# controller_board.net
KiCad netlist of a schematic drawn in EAGLE
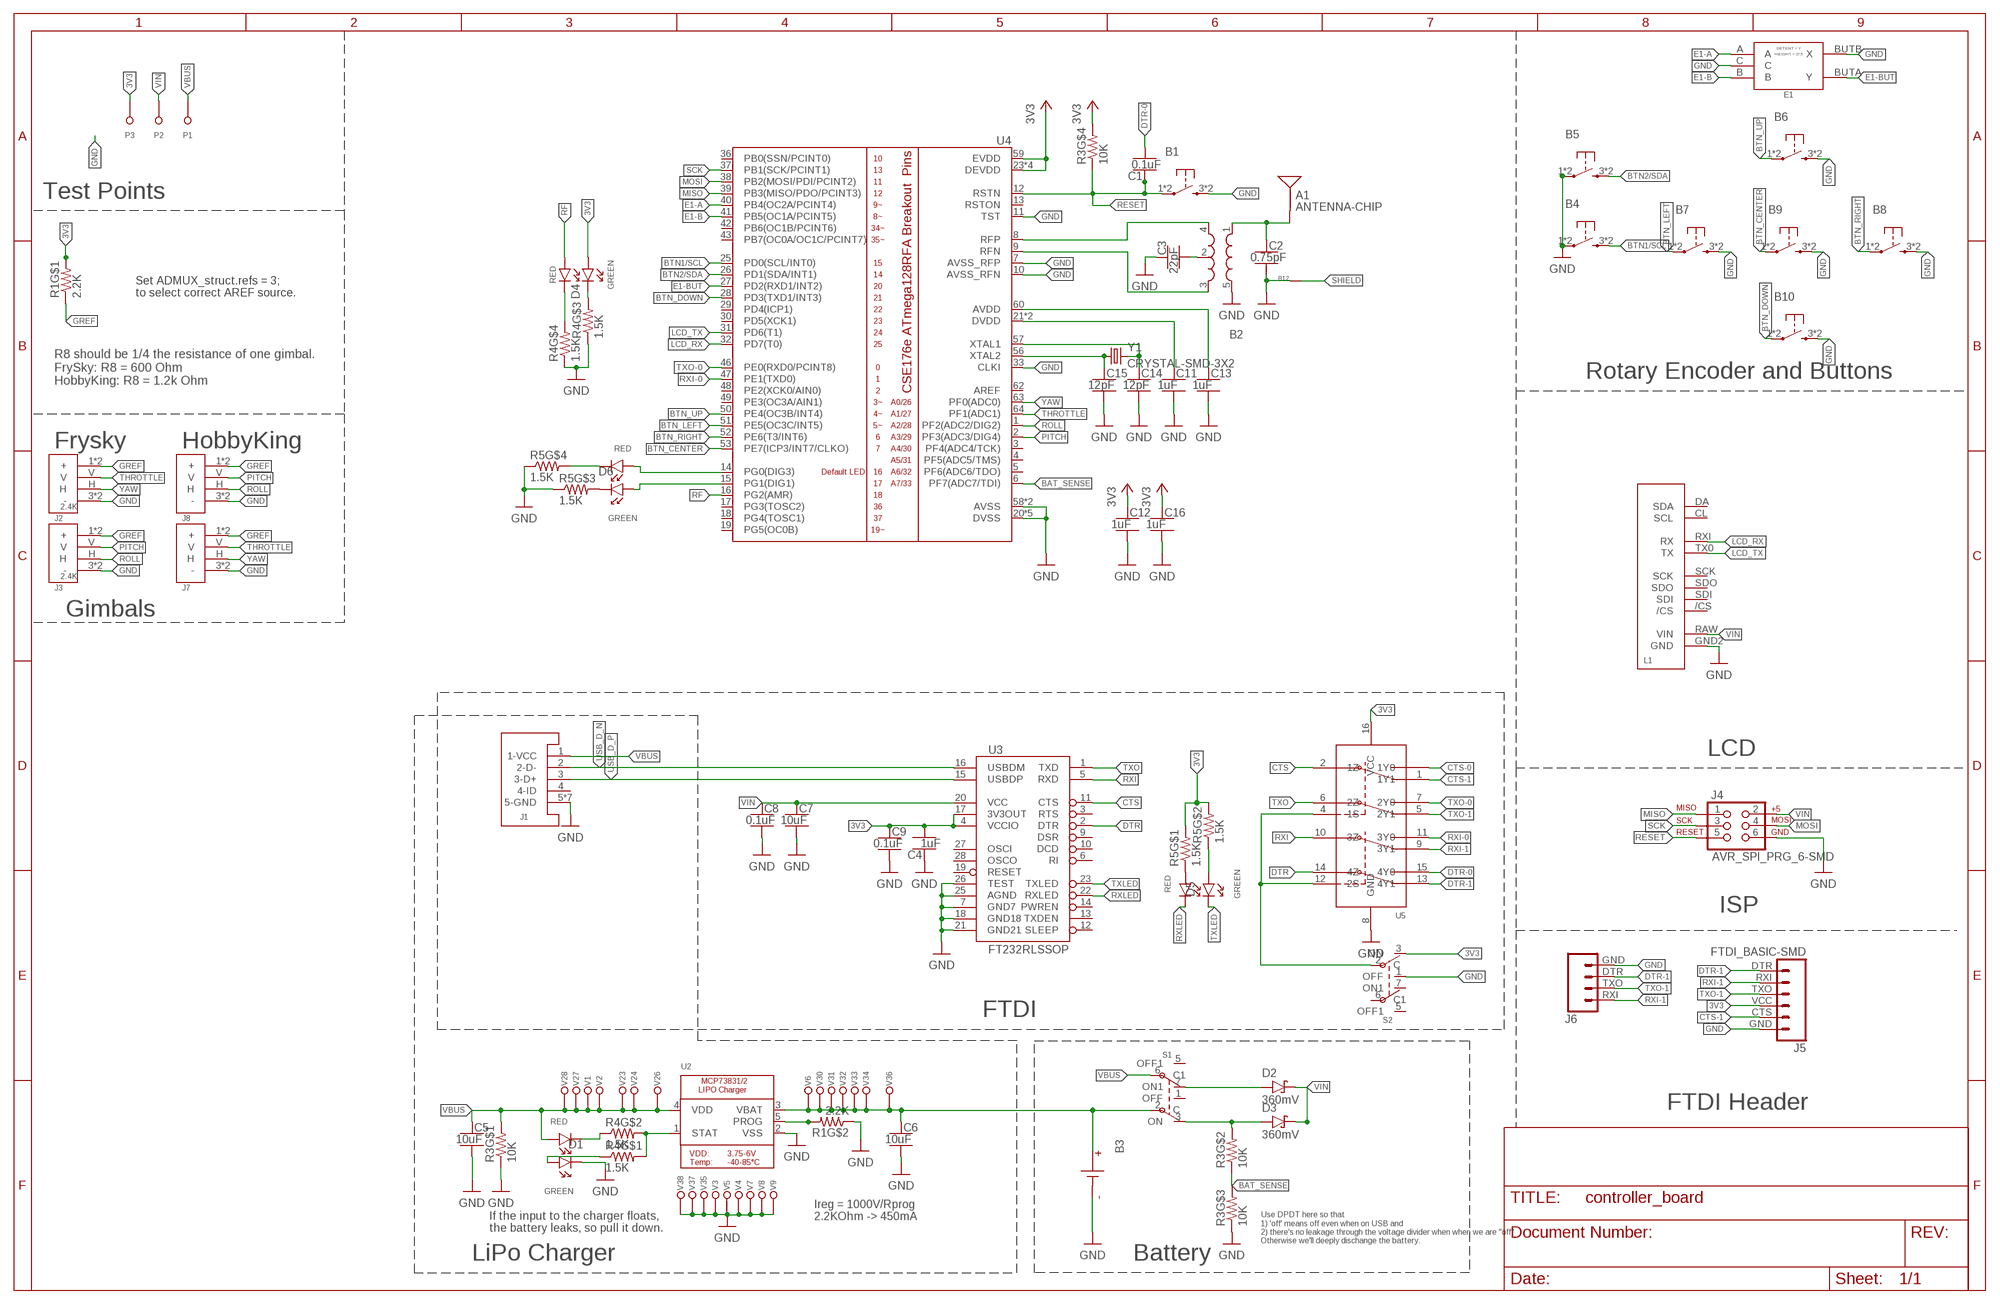
[diagram p0: schematic, sheet 1]

(export (version "E")
  (design (tool "Eeschema 10.0.6"))
  (components
    (comp (ref "A1")
      (value "ANTENNA-CHIP")
      (footprint "eagle-import:ANTENNA-CHIP")
      (fields (field (name "MFR") "Linx Technologies Inc.") (field (name "MPN") "ANT-2.45-CHP-T"))
      (libsource (lib "eagle-import") (part "ANTENNA-CHIP"))
    )
    (comp (ref "B1")
      (value "PUSHBUTTON_-4.5X4.5")
      (footprint "eagle-import:4.5MM_TACTILE_SWITCH_TL3305AF160QG")
      (fields (field (name "MFR") "E-Switch") (field (name "MPN") "TL3305AF160QG"))
      (libsource (lib "eagle-import") (part "PUSHBUTTON_-4.5X4.5"))
    )
    (comp (ref "B2")
      (value "BALUN0805")
      (footprint "eagle-import:BALUN")
      (fields (field (name "MFR") "Wurth Electronics Inc.") (field (name "MPN") "748421245"))
      (libsource (lib "eagle-import") (part "BALUN0805"))
    )
    (comp (ref "B3")
      (value "BATTERY-SMD")
      (footprint "eagle-import:MOLEX-BATTERY-CONNECTOR-SMD-51005-2P")
      (fields (field (name "MFR") "UNKNOWN"))
      (libsource (lib "eagle-import") (part "BATTERY-SMD"))
    )
    (comp (ref "B4")
      (value "PUSHBUTTON_-4.5X4.5")
      (footprint "eagle-import:4.5MM_TACTILE_SWITCH_TL3305AF160QG")
      (fields (field (name "MFR") "E-Switch") (field (name "MPN") "TL3305AF160QG"))
      (libsource (lib "eagle-import") (part "PUSHBUTTON_-4.5X4.5"))
    )
    (comp (ref "B5")
      (value "PUSHBUTTON_-4.5X4.5")
      (footprint "eagle-import:4.5MM_TACTILE_SWITCH_TL3305AF160QG")
      (fields (field (name "MFR") "E-Switch") (field (name "MPN") "TL3305AF160QG"))
      (libsource (lib "eagle-import") (part "PUSHBUTTON_-4.5X4.5"))
    )
    (comp (ref "B6")
      (value "PUSHBUTTON_-4.5X4.5")
      (footprint "eagle-import:4.5MM_TACTILE_SWITCH_TL3305AF160QG")
      (fields (field (name "MFR") "E-Switch") (field (name "MPN") "TL3305AF160QG"))
      (libsource (lib "eagle-import") (part "PUSHBUTTON_-4.5X4.5"))
    )
    (comp (ref "B7")
      (value "PUSHBUTTON_-4.5X4.5")
      (footprint "eagle-import:4.5MM_TACTILE_SWITCH_TL3305AF160QG")
      (fields (field (name "MFR") "E-Switch") (field (name "MPN") "TL3305AF160QG"))
      (libsource (lib "eagle-import") (part "PUSHBUTTON_-4.5X4.5"))
    )
    (comp (ref "B8")
      (value "PUSHBUTTON_-4.5X4.5")
      (footprint "eagle-import:4.5MM_TACTILE_SWITCH_TL3305AF160QG")
      (fields (field (name "MFR") "E-Switch") (field (name "MPN") "TL3305AF160QG"))
      (libsource (lib "eagle-import") (part "PUSHBUTTON_-4.5X4.5"))
    )
    (comp (ref "B9")
      (value "PUSHBUTTON_-4.5X4.5")
      (footprint "eagle-import:4.5MM_TACTILE_SWITCH_TL3305AF160QG")
      (fields (field (name "MFR") "E-Switch") (field (name "MPN") "TL3305AF160QG"))
      (libsource (lib "eagle-import") (part "PUSHBUTTON_-4.5X4.5"))
    )
    (comp (ref "B10")
      (value "PUSHBUTTON_-4.5X4.5")
      (footprint "eagle-import:4.5MM_TACTILE_SWITCH_TL3305AF160QG")
      (fields (field (name "MFR") "E-Switch") (field (name "MPN") "TL3305AF160QG"))
      (libsource (lib "eagle-import") (part "PUSHBUTTON_-4.5X4.5"))
    )
    (comp (ref "B12")
      (value "NET_BRIDGE")
      (footprint "eagle-import:NET_BRIDGE")
      (libsource (lib "eagle-import") (part "NET_BRIDGE"))
    )
    (comp (ref "C1")
      (value "0.1uF")
      (footprint "eagle-import:CAPC1608X100")
      (fields (field (name "MFR") "KEMET") (field (name "MPN") "C0603C104K8RACTU"))
      (libsource (lib "eagle-import") (part "CAPACITOR-NP_SMD-0603_CERAMIC-0.1UF"))
    )
    (comp (ref "C2")
      (value "0.75pF")
      (footprint "eagle-import:CAPC1608X100")
      (fields (field (name "MFR") "Yageo") (field (name "MPN") "CC0603BRNPO9BNR75"))
      (libsource (lib "eagle-import") (part "CAPACITOR-NP_SMD-0603_CERAMIC-0.75PF"))
    )
    (comp (ref "C3")
      (value "22pF")
      (footprint "eagle-import:CAPC1608X100")
      (fields (field (name "MFR") "AVX Corporation") (field (name "MPN") "06036A220KAT2A"))
      (libsource (lib "eagle-import") (part "CAPACITOR-NP_SMD-0603_CERAMIC-22PF"))
    )
    (comp (ref "C4")
      (value "1uF")
      (footprint "eagle-import:CAPC1608X100")
      (fields (field (name "MFR") "Samsung Electro-Mechanics") (field (name "MPN") "CL10A105KP8NNNC"))
      (libsource (lib "eagle-import") (part "CAPACITOR-NP_SMD-0603_CERAMIC-1UF"))
    )
    (comp (ref "C5")
      (value "10uF")
      (footprint "eagle-import:CAPC1608X100")
      (fields (field (name "MFR") "Samsung Electro-Mechanics") (field (name "MPN") "CL10A106MQ8NNNC"))
      (libsource (lib "eagle-import") (part "CAPACITOR-NP_SMD-0603_CERAMIC-10UF"))
    )
    (comp (ref "C6")
      (value "10uF")
      (footprint "eagle-import:CAPC1608X100")
      (fields (field (name "MFR") "Samsung Electro-Mechanics") (field (name "MPN") "CL10A106MQ8NNNC"))
      (libsource (lib "eagle-import") (part "CAPACITOR-NP_SMD-0603_CERAMIC-10UF"))
    )
    (comp (ref "C7")
      (value "10uF")
      (footprint "eagle-import:CAPC1608X100")
      (fields (field (name "MFR") "Samsung Electro-Mechanics") (field (name "MPN") "CL10A106MQ8NNNC"))
      (libsource (lib "eagle-import") (part "CAPACITOR-NP_SMD-0603_CERAMIC-10UF"))
    )
    (comp (ref "C8")
      (value "0.1uF")
      (footprint "eagle-import:CAPC1608X100")
      (fields (field (name "MFR") "KEMET") (field (name "MPN") "C0603C104K8RACTU"))
      (libsource (lib "eagle-import") (part "CAPACITOR-NP_SMD-0603_CERAMIC-0.1UF"))
    )
    (comp (ref "C9")
      (value "0.1uF")
      (footprint "eagle-import:CAPC1608X100")
      (fields (field (name "MFR") "KEMET") (field (name "MPN") "C0603C104K8RACTU"))
      (libsource (lib "eagle-import") (part "CAPACITOR-NP_SMD-0603_CERAMIC-0.1UF"))
    )
    (comp (ref "C11")
      (value "1uF")
      (footprint "eagle-import:CAPC1608X100")
      (fields (field (name "MFR") "Samsung Electro-Mechanics") (field (name "MPN") "CL10A105KP8NNNC"))
      (libsource (lib "eagle-import") (part "CAPACITOR-NP_SMD-0603_CERAMIC-1UF"))
    )
    (comp (ref "C12")
      (value "1uF")
      (footprint "eagle-import:CAPC1608X100")
      (fields (field (name "MFR") "Samsung Electro-Mechanics") (field (name "MPN") "CL10A105KP8NNNC"))
      (libsource (lib "eagle-import") (part "CAPACITOR-NP_SMD-0603_CERAMIC-1UF"))
    )
    (comp (ref "C13")
      (value "1uF")
      (footprint "eagle-import:CAPC1608X100")
      (fields (field (name "MFR") "Samsung Electro-Mechanics") (field (name "MPN") "CL10A105KP8NNNC"))
      (libsource (lib "eagle-import") (part "CAPACITOR-NP_SMD-0603_CERAMIC-1UF"))
    )
    (comp (ref "C14")
      (value "12pF")
      (footprint "eagle-import:CAPC1608X100")
      (fields (field (name "MFR") "Vishay Vitramon") (field (name "MPN") "VJ0603A120FXQCW1BC"))
      (libsource (lib "eagle-import") (part "CAPACITOR-NP_SMD-0603_CERAMIC-12PF"))
    )
    (comp (ref "C15")
      (value "12pF")
      (footprint "eagle-import:CAPC1608X100")
      (fields (field (name "MFR") "Vishay Vitramon") (field (name "MPN") "VJ0603A120FXQCW1BC"))
      (libsource (lib "eagle-import") (part "CAPACITOR-NP_SMD-0603_CERAMIC-12PF"))
    )
    (comp (ref "C16")
      (value "1uF")
      (footprint "eagle-import:CAPC1608X100")
      (fields (field (name "MFR") "Samsung Electro-Mechanics") (field (name "MPN") "CL10A105KP8NNNC"))
      (libsource (lib "eagle-import") (part "CAPACITOR-NP_SMD-0603_CERAMIC-1UF"))
    )
    (comp (ref "D1")
      (value "LED-2X-GREEN/RED-1.6X1.5MM")
      (footprint "eagle-import:LED-2X-LITE-ON-1.6MMX1.5MM")
      (fields
        (field (name "COLOR2") "GREEN")
        (field (name "COLOR1") "RED")
        (field (name "MFR") "Lite-On Inc.")
        (field (name "MPN") "LTST-C195TGKRKT")
      )
      (libsource (lib "eagle-import") (part "LED-2X-GREEN/RED-1.6X1.5MM"))
    )
    (comp (ref "D2")
      (value "360mV")
      (footprint "eagle-import:SODFL3516X96")
      (fields
        (field (name "MFR") "Toshiba Semiconductor and Storage")
        (field (name "MPN") "CRS08(TE85L,Q,M)")
      )
      (libsource (lib "eagle-import") (part "DIODE-SCHOTTKY_-SMD-SOD123"))
    )
    (comp (ref "D3")
      (value "360mV")
      (footprint "eagle-import:SODFL3516X96")
      (fields
        (field (name "MFR") "Toshiba Semiconductor and Storage")
        (field (name "MPN") "CRS08(TE85L,Q,M)")
      )
      (libsource (lib "eagle-import") (part "DIODE-SCHOTTKY_-SMD-SOD123"))
    )
    (comp (ref "D4")
      (value "LED-2X-GREEN/RED-1.6X1.5MM")
      (footprint "eagle-import:LED-2X-LITE-ON-1.6MMX1.5MM")
      (fields
        (field (name "COLOR2") "GREEN")
        (field (name "COLOR1") "RED")
        (field (name "MFR") "Lite-On Inc.")
        (field (name "MPN") "LTST-C195TGKRKT")
      )
      (libsource (lib "eagle-import") (part "LED-2X-GREEN/RED-1.6X1.5MM"))
    )
    (comp (ref "D5")
      (value "LED-2X-GREEN/RED-1.6X1.5MM")
      (footprint "eagle-import:LED-2X-LITE-ON-1.6MMX1.5MM")
      (fields
        (field (name "COLOR2") "GREEN")
        (field (name "COLOR1") "RED")
        (field (name "MFR") "Lite-On Inc.")
        (field (name "MPN") "LTST-C195TGKRKT")
      )
      (libsource (lib "eagle-import") (part "LED-2X-GREEN/RED-1.6X1.5MM"))
    )
    (comp (ref "D6")
      (value "LED-2X-GREEN/RED-1.6X1.5MM")
      (footprint "eagle-import:LED-2X-LITE-ON-1.6MMX1.5MM")
      (fields
        (field (name "COLOR2") "GREEN")
        (field (name "COLOR1") "RED")
        (field (name "MFR") "Lite-On Inc.")
        (field (name "MPN") "LTST-C195TGKRKT")
      )
      (libsource (lib "eagle-import") (part "LED-2X-GREEN/RED-1.6X1.5MM"))
    )
    (comp (ref "E1")
      (value "ROTARY-ENCODER-W/BUTTON-BOURNS-PEC12R-4217F")
      (footprint "eagle-import:BOURNS-PEC12R")
      (fields (field (name "DETENT") "Y") (field (name "HEIGHT") "17.5"))
      (libsource (lib "eagle-import") (part "ROTARY-ENCODER-W/BUTTON-BOURNS-PEC12R-4217F"))
    )
    (comp (ref "J1")
      (value "USB-MICROA-AMPHENOL-10118192-0001LF")
      (footprint "eagle-import:USB-MICROA-10118192-0001LF")
      (fields (field (name "MFR") "Amphenol ICC (FCI)") (field (name "MPN") "10118192-0001LF"))
      (libsource (lib "eagle-import") (part "USB-MICROA-AMPHENOL-10118192-0001LF"))
    )
    (comp (ref "J2")
      (value "2.4K")
      (footprint "eagle-import:JST-13-PTH")
      (fields (field (name "MFR") "TE Connectivity AMP Connectors") (field (name "MPN") "1-1735446-2"))
      (libsource (lib "eagle-import") (part "FRSKY-GIMBAL-FRYSKY"))
    )
    (comp (ref "J3")
      (value "2.4K")
      (footprint "eagle-import:JST-13-PTH")
      (fields
        (field (name "MFR") "TE Connectivity AMP Connectors")
        (field (name "MPN") "1-1735446-2")
        (field (name "SPICEPREFIX") "E")
      )
      (libsource (lib "eagle-import") (part "FRSKY-GIMBAL-FRYSKY"))
    )
    (comp (ref "J4")
      (value "AVR_SPI_PRG_6-SMD")
      (footprint "eagle-import:2X3-SMD")
      (fields (field (name "MFR") "Amphenol ICC (FCI)") (field (name "MPN") "95278-101A06LF"))
      (libsource (lib "eagle-import") (part "AVR_SPI_PRG_6-SMD"))
    )
    (comp (ref "J5")
      (value "FTDI_BASIC-SMD")
      (footprint "eagle-import:FTDI-BASIC-SMD")
      (fields (field (name "MFR") "Harwin Inc.") (field (name "MPN") "M20-8890645"))
      (libsource (lib "eagle-import") (part "FTDI_BASIC-SMD"))
    )
    (comp (ref "J6")
      (value "FTDI-4PIN-RIGHT-ANGLE-SMD")
      (footprint "eagle-import:HEADER-2X2-0.1IN-MALE-RIGHT-ANGLE-SMD")
      (fields (field (name "MFR") "Samtec Inc.") (field (name "MPN") "TSM-102-01-L-DH"))
      (libsource (lib "eagle-import") (part "FTDI-4PIN-RIGHT-ANGLE-SMD"))
    )
    (comp (ref "J7")
      (value "FRSKY-GIMBAL-2X-SERVO-SMD")
      (footprint "eagle-import:2X-SERVO-SMD")
      (fields (field (name "MFR") "Harwin Inc.") (field (name "MPN") "M20-8890645"))
      (libsource (lib "eagle-import") (part "FRSKY-GIMBAL-2X-SERVO-SMD"))
    )
    (comp (ref "J8")
      (value "FRSKY-GIMBAL-2X-SERVO-SMD")
      (footprint "eagle-import:2X-SERVO-SMD")
      (fields (field (name "MFR") "Harwin Inc.") (field (name "MPN") "M20-8890645"))
      (libsource (lib "eagle-import") (part "FRSKY-GIMBAL-2X-SERVO-SMD"))
    )
    (comp (ref "L1")
      (value "SPARKFUN_SERLCD_SERIAL_REDUCED-SMD")
      (footprint "eagle-import:SPARKFUN_SERLCD_16X2_REDUCED_SMD")
      (fields (field (name "MFR") "Harwin Inc.") (field (name "MPN") "M20-9991045"))
      (libsource (lib "eagle-import") (part "SPARKFUN_SERLCD_SERIAL_REDUCED-SMD"))
    )
    (comp (ref "P1")
      (value "TEST-POINT")
      (footprint "eagle-import:TEST-POINT-KEYSTONE-5000")
      (fields (field (name "MFR") "Keystone Electronics") (field (name "MPN") "5001"))
      (libsource (lib "eagle-import") (part "TEST-POINT"))
    )
    (comp (ref "P2")
      (value "TEST-POINT")
      (footprint "eagle-import:TEST-POINT-KEYSTONE-5000")
      (fields (field (name "MFR") "Keystone Electronics") (field (name "MPN") "5001"))
      (libsource (lib "eagle-import") (part "TEST-POINT"))
    )
    (comp (ref "P3")
      (value "TEST-POINT")
      (footprint "eagle-import:TEST-POINT-KEYSTONE-5000")
      (fields (field (name "MFR") "Keystone Electronics") (field (name "MPN") "5001"))
      (libsource (lib "eagle-import") (part "TEST-POINT"))
    )
    (comp (ref "R1")
      (value "2.2K")
      (footprint "eagle-import:RESCAXS50P200X100X45-8")
      (fields (field (name "MFR") "Panasonic Electronic Components") (field (name "MPN") "EXB-N8V221JX"))
      (libsource (lib "eagle-import") (part "RESISTOR-PACK-4X-2.2K"))
    )
    (comp (ref "R3")
      (value "10K")
      (footprint "eagle-import:RESCAXS50P200X100X45-8")
      (fields (field (name "MFR") "Panasonic Electronic Components") (field (name "MPN") "EXB-N8V103JX"))
      (libsource (lib "eagle-import") (part "RESISTOR-PACK-4X-10K"))
    )
    (comp (ref "R4")
      (value "1.5K")
      (footprint "eagle-import:RESCAXS50P200X100X45-8")
      (fields (field (name "MFR") "Panasonic Electronic Components") (field (name "MPN") "EXB-N8V152JX"))
      (libsource (lib "eagle-import") (part "RESISTOR-PACK-4X-1.5K"))
    )
    (comp (ref "R5")
      (value "1.5K")
      (footprint "eagle-import:RESCAXS50P200X100X45-8")
      (fields (field (name "MFR") "Panasonic Electronic Components") (field (name "MPN") "EXB-N8V152JX"))
      (libsource (lib "eagle-import") (part "RESISTOR-PACK-4X-1.5K"))
    )
    (comp (ref "S1")
      (value "SWITCH-DPDT-300MA-6V-SMD")
      (footprint "eagle-import:JS202011JCQN")
      (fields (field (name "MFR") "C&K") (field (name "MPN") "JS202011JCQN"))
      (libsource (lib "eagle-import") (part "SWITCH-DPDT-300MA-6V-SMD"))
    )
    (comp (ref "S2")
      (value "SWITCH-DPDT-300MA-6V-SMD")
      (footprint "eagle-import:JS202011JCQN")
      (fields (field (name "MFR") "C&K") (field (name "MPN") "JS202011JCQN"))
      (libsource (lib "eagle-import") (part "SWITCH-DPDT-300MA-6V-SMD"))
    )
    (comp (ref "U2")
      (value "MCP73831T-2ACI/OT")
      (footprint "eagle-import:SOT23-5")
      (fields (field (name "MFR") "Microchip Technology"))
      (libsource (lib "eagle-import") (part "MCP73831/2"))
    )
    (comp (ref "U3")
      (value "FT232RLSSOP")
      (footprint "eagle-import:SSOP28DB")
      (fields (field (name "MFR") "FTDI") (field (name "MPN") "FT232RL-REEL"))
      (libsource (lib "eagle-import") (part "FT232RLSSOP"))
    )
    (comp (ref "U4")
      (value "ATMEGA128RFA1")
      (footprint "eagle-import:QFN-64")
      (fields (field (name "MFR") "Microchip Technology") (field (name "MPN") "ATMEGA128RFA1-ZU"))
      (libsource (lib "eagle-import") (part "ATMEGA128RFA1"))
    )
    (comp (ref "U5")
      (value "DPDT-X2")
      (footprint "eagle-import:SOP65P640X110-16")
      (fields (field (name "MFR") "NXP USA Inc.") (field (name "MPN") "NX3L2467PW,118"))
      (libsource (lib "eagle-import") (part "DPDT-X2"))
    )
    (comp (ref "V1")
      (value "LOCKED-VIA-0.2")
      (footprint "eagle-import:VIA-0.2MM")
      (libsource (lib "eagle-import") (part "LOCKED-VIA-0.2"))
    )
    (comp (ref "V2")
      (value "LOCKED-VIA-0.2")
      (footprint "eagle-import:VIA-0.2MM")
      (libsource (lib "eagle-import") (part "LOCKED-VIA-0.2"))
    )
    (comp (ref "V3")
      (value "LOCKED-VIA-0.2")
      (footprint "eagle-import:VIA-0.2MM")
      (libsource (lib "eagle-import") (part "LOCKED-VIA-0.2"))
    )
    (comp (ref "V4")
      (value "LOCKED-VIA-0.2")
      (footprint "eagle-import:VIA-0.2MM")
      (libsource (lib "eagle-import") (part "LOCKED-VIA-0.2"))
    )
    (comp (ref "V5")
      (value "LOCKED-VIA-0.2")
      (footprint "eagle-import:VIA-0.2MM")
      (libsource (lib "eagle-import") (part "LOCKED-VIA-0.2"))
    )
    (comp (ref "V6")
      (value "LOCKED-VIA-0.2")
      (footprint "eagle-import:VIA-0.2MM")
      (libsource (lib "eagle-import") (part "LOCKED-VIA-0.2"))
    )
    (comp (ref "V7")
      (value "LOCKED-VIA-0.2")
      (footprint "eagle-import:VIA-0.2MM")
      (libsource (lib "eagle-import") (part "LOCKED-VIA-0.2"))
    )
    (comp (ref "V8")
      (value "LOCKED-VIA-0.2")
      (footprint "eagle-import:VIA-0.2MM")
      (libsource (lib "eagle-import") (part "LOCKED-VIA-0.2"))
    )
    (comp (ref "V9")
      (value "LOCKED-VIA-0.2")
      (footprint "eagle-import:VIA-0.2MM")
      (libsource (lib "eagle-import") (part "LOCKED-VIA-0.2"))
    )
    (comp (ref "V23")
      (value "LOCKED-VIA-0.2")
      (footprint "eagle-import:VIA-0.2MM")
      (libsource (lib "eagle-import") (part "LOCKED-VIA-0.2"))
    )
    (comp (ref "V24")
      (value "LOCKED-VIA-0.2")
      (footprint "eagle-import:VIA-0.2MM")
      (libsource (lib "eagle-import") (part "LOCKED-VIA-0.2"))
    )
    (comp (ref "V26")
      (value "LOCKED-VIA-0.2")
      (footprint "eagle-import:VIA-0.2MM")
      (libsource (lib "eagle-import") (part "LOCKED-VIA-0.2"))
    )
    (comp (ref "V27")
      (value "LOCKED-VIA-0.2")
      (footprint "eagle-import:VIA-0.2MM")
      (libsource (lib "eagle-import") (part "LOCKED-VIA-0.2"))
    )
    (comp (ref "V28")
      (value "LOCKED-VIA-0.2")
      (footprint "eagle-import:VIA-0.2MM")
      (libsource (lib "eagle-import") (part "LOCKED-VIA-0.2"))
    )
    (comp (ref "V30")
      (value "LOCKED-VIA-0.2")
      (footprint "eagle-import:VIA-0.2MM")
      (libsource (lib "eagle-import") (part "LOCKED-VIA-0.2"))
    )
    (comp (ref "V31")
      (value "LOCKED-VIA-0.2")
      (footprint "eagle-import:VIA-0.2MM")
      (libsource (lib "eagle-import") (part "LOCKED-VIA-0.2"))
    )
    (comp (ref "V32")
      (value "LOCKED-VIA-0.2")
      (footprint "eagle-import:VIA-0.2MM")
      (libsource (lib "eagle-import") (part "LOCKED-VIA-0.2"))
    )
    (comp (ref "V33")
      (value "LOCKED-VIA-0.2")
      (footprint "eagle-import:VIA-0.2MM")
      (libsource (lib "eagle-import") (part "LOCKED-VIA-0.2"))
    )
    (comp (ref "V34")
      (value "LOCKED-VIA-0.2")
      (footprint "eagle-import:VIA-0.2MM")
      (libsource (lib "eagle-import") (part "LOCKED-VIA-0.2"))
    )
    (comp (ref "V35")
      (value "LOCKED-VIA-0.2")
      (footprint "eagle-import:VIA-0.2MM")
      (libsource (lib "eagle-import") (part "LOCKED-VIA-0.2"))
    )
    (comp (ref "V36")
      (value "LOCKED-VIA-0.2")
      (footprint "eagle-import:VIA-0.2MM")
      (libsource (lib "eagle-import") (part "LOCKED-VIA-0.2"))
    )
    (comp (ref "V37")
      (value "LOCKED-VIA-0.2")
      (footprint "eagle-import:VIA-0.2MM")
      (libsource (lib "eagle-import") (part "LOCKED-VIA-0.2"))
    )
    (comp (ref "V38")
      (value "LOCKED-VIA-0.2")
      (footprint "eagle-import:VIA-0.2MM")
      (libsource (lib "eagle-import") (part "LOCKED-VIA-0.2"))
    )
    (comp (ref "Y1")
      (value "CRYSTAL-SMD-3X2")
      (footprint "eagle-import:OSCCC320X250X85")
      (fields (field (name "MFR") "Abracon LLC") (field (name "MPN") "ABM8-16.000MHZ-B2-T"))
      (libsource (lib "eagle-import") (part "CRYSTAL-SMD-3X2"))
    )
  )
  (nets
    (net (code "1") (name "3V3") (class "Default")
      (node (ref "C12") (pin "1") (pinfunction "1_1") (pintype "passive"))
      (node (ref "C16") (pin "1") (pinfunction "1_1") (pintype "passive"))
      (node (ref "C4") (pin "2") (pinfunction "2_2") (pintype "passive"))
      (node (ref "C9") (pin "1") (pinfunction "1_1") (pintype "passive"))
      (node (ref "D4") (pin "A1") (pinfunction "A1_A1") (pintype "passive"))
      (node (ref "J5") (pin "VCC") (pinfunction "4_VCC") (pintype "passive"))
      (node (ref "P3") (pin "T") (pinfunction "T_T") (pintype "bidirectional"))
      (node (ref "R1") (pin "5") (pinfunction "2_5") (pintype "passive"))
      (node (ref "R3") (pin "8") (pinfunction "2_8") (pintype "passive"))
      (node (ref "R5") (pin "5") (pinfunction "2_5") (pintype "passive"))
      (node (ref "R5") (pin "6") (pinfunction "2_6") (pintype "passive"))
      (node (ref "S2") (pin "3") (pinfunction "ON_3") (pintype "bidirectional"))
      (node (ref "U3") (pin "17") (pinfunction "3V3OUT_17") (pintype "output"))
      (node (ref "U3") (pin "4") (pinfunction "VCCIO_4") (pintype "power_in"))
      (node (ref "U4") (pin "23") (pinfunction "DEVDD_23") (pintype "bidirectional"))
      (node (ref "U4") (pin "34") (pinfunction "DEVDD_34") (pintype "bidirectional"))
      (node (ref "U4") (pin "44") (pinfunction "DEVDD_44") (pintype "bidirectional"))
      (node (ref "U4") (pin "54") (pinfunction "DEVDD_54") (pintype "bidirectional"))
      (node (ref "U4") (pin "59") (pinfunction "EVDD_59") (pintype "bidirectional"))
      (node (ref "U5") (pin "16") (pinfunction "VCC_16") (pintype "bidirectional"))
    )
    (net (code "2") (name "BAT_SENSE") (class "Default")
      (node (ref "R3") (pin "3") (pinfunction "1_3") (pintype "passive"))
      (node (ref "R3") (pin "7") (pinfunction "2_7") (pintype "passive"))
      (node (ref "U4") (pin "6") (pinfunction "PF7(ADC7/TDI)_6") (pintype "bidirectional"))
    )
    (net (code "3") (name "BTN1{slash}SCL") (class "Default")
      (node (ref "B4") (pin "3") (pinfunction "2_3") (pintype "passive"))
      (node (ref "B4") (pin "4") (pinfunction "2_4") (pintype "passive"))
      (node (ref "U4") (pin "25") (pinfunction "PD0(SCL/INT0)_25") (pintype "bidirectional"))
    )
    (net (code "4") (name "BTN2{slash}SDA") (class "Default")
      (node (ref "B5") (pin "3") (pinfunction "2_3") (pintype "passive"))
      (node (ref "B5") (pin "4") (pinfunction "2_4") (pintype "passive"))
      (node (ref "U4") (pin "26") (pinfunction "PD1(SDA/INT1)_26") (pintype "bidirectional"))
    )
    (net (code "5") (name "BTN_CENTER") (class "Default")
      (node (ref "B9") (pin "1") (pinfunction "1_1") (pintype "passive"))
      (node (ref "B9") (pin "2") (pinfunction "1_2") (pintype "passive"))
      (node (ref "U4") (pin "53") (pinfunction "PE7(ICP3/INT7/CLKO)_53") (pintype "bidirectional"))
    )
    (net (code "6") (name "BTN_DOWN") (class "Default")
      (node (ref "B10") (pin "1") (pinfunction "1_1") (pintype "passive"))
      (node (ref "B10") (pin "2") (pinfunction "1_2") (pintype "passive"))
      (node (ref "U4") (pin "28") (pinfunction "PD3(TXD1/INT3)_28") (pintype "bidirectional"))
    )
    (net (code "7") (name "BTN_LEFT") (class "Default")
      (node (ref "B7") (pin "1") (pinfunction "1_1") (pintype "passive"))
      (node (ref "B7") (pin "2") (pinfunction "1_2") (pintype "passive"))
      (node (ref "U4") (pin "51") (pinfunction "PE5(OC3C/INT5)_51") (pintype "bidirectional"))
    )
    (net (code "8") (name "BTN_RIGHT") (class "Default")
      (node (ref "B8") (pin "1") (pinfunction "1_1") (pintype "passive"))
      (node (ref "B8") (pin "2") (pinfunction "1_2") (pintype "passive"))
      (node (ref "U4") (pin "52") (pinfunction "PE6(T3/INT6)_52") (pintype "bidirectional"))
    )
    (net (code "9") (name "BTN_UP") (class "Default")
      (node (ref "B6") (pin "1") (pinfunction "1_1") (pintype "passive"))
      (node (ref "B6") (pin "2") (pinfunction "1_2") (pintype "passive"))
      (node (ref "U4") (pin "50") (pinfunction "PE4(OC3B/INT4)_50") (pintype "bidirectional"))
    )
    (net (code "10") (name "CTS") (class "Default")
      (node (ref "U3") (pin "11") (pinfunction "CTS_11") (pintype "input"))
      (node (ref "U5") (pin "2") (pinfunction "1Z_2") (pintype "bidirectional"))
    )
    (net (code "11") (name "CTS-0") (class "Default")
      (node (ref "U5") (pin "3") (pinfunction "1Y0_3") (pintype "bidirectional"))
    )
    (net (code "12") (name "CTS-1") (class "Default")
      (node (ref "J5") (pin "CTS") (pinfunction "5_CTS") (pintype "passive"))
      (node (ref "U5") (pin "1") (pinfunction "1Y1_1") (pintype "bidirectional"))
    )
    (net (code "13") (name "DTR") (class "Default")
      (node (ref "U3") (pin "2") (pinfunction "DTR_2") (pintype "output"))
      (node (ref "U5") (pin "14") (pinfunction "4Z_14") (pintype "bidirectional"))
    )
    (net (code "14") (name "DTR-0") (class "Default")
      (node (ref "C1") (pin "2") (pinfunction "2_2") (pintype "passive"))
      (node (ref "U5") (pin "15") (pinfunction "4Y0_15") (pintype "bidirectional"))
    )
    (net (code "15") (name "DTR-1") (class "Default")
      (node (ref "J5") (pin "DTR") (pinfunction "1_DTR") (pintype "passive"))
      (node (ref "J6") (pin "DTR") (pinfunction "3_DTR") (pintype "bidirectional"))
      (node (ref "U5") (pin "13") (pinfunction "4Y1_13") (pintype "bidirectional"))
    )
    (net (code "16") (name "E1-A") (class "Default")
      (node (ref "E1") (pin "A") (pinfunction "A_A") (pintype "bidirectional"))
      (node (ref "U4") (pin "40") (pinfunction "PB4(OC2A/PCINT4)_40") (pintype "bidirectional"))
    )
    (net (code "17") (name "E1-B") (class "Default")
      (node (ref "E1") (pin "B") (pinfunction "B_B") (pintype "bidirectional"))
      (node (ref "U4") (pin "41") (pinfunction "PB5(OC1A/PCINT5)_41") (pintype "bidirectional"))
    )
    (net (code "18") (name "E1-BUT") (class "Default")
      (node (ref "E1") (pin "BUTA") (pinfunction "Y_BUTA") (pintype "bidirectional"))
      (node (ref "U4") (pin "27") (pinfunction "PD2(RXD1/INT2)_27") (pintype "bidirectional"))
    )
    (net (code "19") (name "GND") (class "Default")
      (node (ref "B1") (pin "3") (pinfunction "2_3") (pintype "passive"))
      (node (ref "B1") (pin "4") (pinfunction "2_4") (pintype "passive"))
      (node (ref "B10") (pin "3") (pinfunction "2_3") (pintype "passive"))
      (node (ref "B10") (pin "4") (pinfunction "2_4") (pintype "passive"))
      (node (ref "B12") (pin "P1") (pinfunction "P1_P1") (pintype "bidirectional"))
      (node (ref "B2") (pin "5") (pinfunction "GND_5") (pintype "bidirectional"))
      (node (ref "B3") (pin "G") (pinfunction "N_G") (pintype "bidirectional"))
      (node (ref "B3") (pin "G2") (pinfunction "N_G2") (pintype "bidirectional"))
      (node (ref "B3") (pin "G3") (pinfunction "N_G3") (pintype "bidirectional"))
      (node (ref "B4") (pin "1") (pinfunction "1_1") (pintype "passive"))
      (node (ref "B4") (pin "2") (pinfunction "1_2") (pintype "passive"))
      (node (ref "B5") (pin "1") (pinfunction "1_1") (pintype "passive"))
      (node (ref "B5") (pin "2") (pinfunction "1_2") (pintype "passive"))
      (node (ref "B6") (pin "3") (pinfunction "2_3") (pintype "passive"))
      (node (ref "B6") (pin "4") (pinfunction "2_4") (pintype "passive"))
      (node (ref "B7") (pin "3") (pinfunction "2_3") (pintype "passive"))
      (node (ref "B7") (pin "4") (pinfunction "2_4") (pintype "passive"))
      (node (ref "B8") (pin "3") (pinfunction "2_3") (pintype "passive"))
      (node (ref "B8") (pin "4") (pinfunction "2_4") (pintype "passive"))
      (node (ref "B9") (pin "3") (pinfunction "2_3") (pintype "passive"))
      (node (ref "B9") (pin "4") (pinfunction "2_4") (pintype "passive"))
      (node (ref "C11") (pin "2") (pinfunction "2_2") (pintype "passive"))
      (node (ref "C12") (pin "2") (pinfunction "2_2") (pintype "passive"))
      (node (ref "C13") (pin "2") (pinfunction "2_2") (pintype "passive"))
      (node (ref "C14") (pin "2") (pinfunction "2_2") (pintype "passive"))
      (node (ref "C15") (pin "2") (pinfunction "2_2") (pintype "passive"))
      (node (ref "C16") (pin "2") (pinfunction "2_2") (pintype "passive"))
      (node (ref "C2") (pin "2") (pinfunction "2_2") (pintype "passive"))
      (node (ref "C3") (pin "1") (pinfunction "1_1") (pintype "passive"))
      (node (ref "C4") (pin "1") (pinfunction "1_1") (pintype "passive"))
      (node (ref "C5") (pin "2") (pinfunction "2_2") (pintype "passive"))
      (node (ref "C6") (pin "2") (pinfunction "2_2") (pintype "passive"))
      (node (ref "C7") (pin "2") (pinfunction "2_2") (pintype "passive"))
      (node (ref "C8") (pin "2") (pinfunction "2_2") (pintype "passive"))
      (node (ref "C9") (pin "2") (pinfunction "2_2") (pintype "passive"))
      (node (ref "D1") (pin "C1") (pinfunction "C1_C1") (pintype "passive"))
      (node (ref "E1") (pin "BUTB") (pinfunction "X_BUTB") (pintype "bidirectional"))
      (node (ref "E1") (pin "C") (pinfunction "C_C") (pintype "bidirectional"))
      (node (ref "J1") (pin "10") (pinfunction "5-GND_10") (pintype "bidirectional"))
      (node (ref "J1") (pin "11") (pinfunction "5-GND_11") (pintype "bidirectional"))
      (node (ref "J1") (pin "5") (pinfunction "5-GND_5") (pintype "bidirectional"))
      (node (ref "J1") (pin "6") (pinfunction "5-GND_6") (pintype "bidirectional"))
      (node (ref "J1") (pin "7") (pinfunction "5-GND_7") (pintype "bidirectional"))
      (node (ref "J1") (pin "8") (pinfunction "5-GND_8") (pintype "bidirectional"))
      (node (ref "J1") (pin "9") (pinfunction "5-GND_9") (pintype "bidirectional"))
      (node (ref "J2") (pin "3") (pinfunction "-_3") (pintype "bidirectional"))
      (node (ref "J2") (pin "6") (pinfunction "-_6") (pintype "bidirectional"))
      (node (ref "J3") (pin "3") (pinfunction "-_3") (pintype "bidirectional"))
      (node (ref "J3") (pin "6") (pinfunction "-_6") (pintype "bidirectional"))
      (node (ref "J4") (pin "6") (pinfunction "6_6") (pintype "passive"))
      (node (ref "J5") (pin "GND") (pinfunction "6_GND") (pintype "passive"))
      (node (ref "J6") (pin "GND") (pinfunction "4_GND") (pintype "bidirectional"))
      (node (ref "J7") (pin "3") (pinfunction "-_3") (pintype "bidirectional"))
      (node (ref "J7") (pin "6") (pinfunction "-_6") (pintype "bidirectional"))
      (node (ref "J8") (pin "3") (pinfunction "-_3") (pintype "bidirectional"))
      (node (ref "J8") (pin "6") (pinfunction "-_6") (pintype "bidirectional"))
      (node (ref "L1") (pin "GND2") (pinfunction "GND_GND2") (pintype "bidirectional"))
      (node (ref "R1") (pin "3") (pinfunction "1_3") (pintype "passive"))
      (node (ref "R3") (pin "2") (pinfunction "1_2") (pintype "passive"))
      (node (ref "R3") (pin "4") (pinfunction "1_4") (pintype "passive"))
      (node (ref "R4") (pin "1") (pinfunction "1_1") (pintype "passive"))
      (node (ref "R4") (pin "2") (pinfunction "1_2") (pintype "passive"))
      (node (ref "R5") (pin "1") (pinfunction "1_1") (pintype "passive"))
      (node (ref "R5") (pin "2") (pinfunction "1_2") (pintype "passive"))
      (node (ref "S2") (pin "1") (pinfunction "OFF_1") (pintype "bidirectional"))
      (node (ref "U2") (pin "2") (pinfunction "VSS_2") (pintype "power_in"))
      (node (ref "U3") (pin "18") (pinfunction "GND18_18") (pintype "power_in"))
      (node (ref "U3") (pin "21") (pinfunction "GND21_21") (pintype "power_in"))
      (node (ref "U3") (pin "25") (pinfunction "AGND_25") (pintype "power_in"))
      (node (ref "U3") (pin "26") (pinfunction "TEST_26") (pintype "input"))
      (node (ref "U3") (pin "7") (pinfunction "GND7_7") (pintype "power_in"))
      (node (ref "U4") (pin "10") (pinfunction "AVSS_RFN_10") (pintype "bidirectional"))
      (node (ref "U4") (pin "11") (pinfunction "TST_11") (pintype "bidirectional"))
      (node (ref "U4") (pin "20") (pinfunction "DVSS_20") (pintype "bidirectional"))
      (node (ref "U4") (pin "24") (pinfunction "DVSS_24") (pintype "bidirectional"))
      (node (ref "U4") (pin "33") (pinfunction "CLKI_33") (pintype "bidirectional"))
      (node (ref "U4") (pin "35") (pinfunction "DVSS_35") (pintype "bidirectional"))
      (node (ref "U4") (pin "45") (pinfunction "DVSS_45") (pintype "bidirectional"))
      (node (ref "U4") (pin "55") (pinfunction "DVSS_55") (pintype "bidirectional"))
      (node (ref "U4") (pin "58") (pinfunction "AVSS_58") (pintype "bidirectional"))
      (node (ref "U4") (pin "61") (pinfunction "AVSS_61") (pintype "bidirectional"))
      (node (ref "U4") (pin "7") (pinfunction "AVSS_RFP_7") (pintype "bidirectional"))
      (node (ref "U5") (pin "8") (pinfunction "GND_8") (pintype "bidirectional"))
      (node (ref "V3") (pin "P1") (pinfunction "N_P1") (pintype "bidirectional"))
      (node (ref "V35") (pin "P1") (pinfunction "N_P1") (pintype "bidirectional"))
      (node (ref "V37") (pin "P1") (pinfunction "N_P1") (pintype "bidirectional"))
      (node (ref "V38") (pin "P1") (pinfunction "N_P1") (pintype "bidirectional"))
      (node (ref "V4") (pin "P1") (pinfunction "N_P1") (pintype "bidirectional"))
      (node (ref "V5") (pin "P1") (pinfunction "N_P1") (pintype "bidirectional"))
      (node (ref "V7") (pin "P1") (pinfunction "N_P1") (pintype "bidirectional"))
      (node (ref "V8") (pin "P1") (pinfunction "N_P1") (pintype "bidirectional"))
      (node (ref "V9") (pin "P1") (pinfunction "N_P1") (pintype "bidirectional"))
    )
    (net (code "20") (name "GREF") (class "Default")
      (node (ref "J2") (pin "1") (pinfunction "+_1") (pintype "bidirectional"))
      (node (ref "J2") (pin "4") (pinfunction "+_4") (pintype "bidirectional"))
      (node (ref "J3") (pin "1") (pinfunction "+_1") (pintype "bidirectional"))
      (node (ref "J3") (pin "4") (pinfunction "+_4") (pintype "bidirectional"))
      (node (ref "J7") (pin "1") (pinfunction "+_1") (pintype "bidirectional"))
      (node (ref "J7") (pin "4") (pinfunction "+_4") (pintype "bidirectional"))
      (node (ref "J8") (pin "1") (pinfunction "+_1") (pintype "bidirectional"))
      (node (ref "J8") (pin "4") (pinfunction "+_4") (pintype "bidirectional"))
      (node (ref "R1") (pin "4") (pinfunction "1_4") (pintype "passive"))
    )
    (net (code "21") (name "LCD_RX") (class "Default")
      (node (ref "L1") (pin "RXI") (pinfunction "RX_RXI") (pintype "bidirectional"))
      (node (ref "U4") (pin "32") (pinfunction "PD7(T0)_32") (pintype "bidirectional"))
    )
    (net (code "22") (name "LCD_TX") (class "Default")
      (node (ref "L1") (pin "TX0") (pinfunction "TX_TX0") (pintype "bidirectional"))
      (node (ref "U4") (pin "31") (pinfunction "PD6(T1)_31") (pintype "bidirectional"))
    )
    (net (code "23") (name "MISO") (class "Default")
      (node (ref "J4") (pin "1") (pinfunction "1_1") (pintype "passive"))
      (node (ref "U4") (pin "39") (pinfunction "PB3(MISO/PDO/PCINT3)_39") (pintype "bidirectional"))
    )
    (net (code "24") (name "MOSI") (class "Default")
      (node (ref "J4") (pin "4") (pinfunction "4_4") (pintype "passive"))
      (node (ref "U4") (pin "38") (pinfunction "PB2(MOSI/PDI/PCINT2)_38") (pintype "bidirectional"))
    )
    (net (code "25") (name "Net-(A1-SIGNAL)") (class "Default")
      (node (ref "A1") (pin "FEED") (pinfunction "SIGNAL_FEED") (pintype "bidirectional"))
      (node (ref "B2") (pin "1") (pinfunction "IN_1") (pintype "bidirectional"))
      (node (ref "C2") (pin "1") (pinfunction "1_1") (pintype "passive"))
    )
    (net (code "26") (name "Net-(B2-GND-Pad2)") (class "Default")
      (node (ref "B2") (pin "2") (pinfunction "GND_2") (pintype "bidirectional"))
      (node (ref "C3") (pin "2") (pinfunction "2_2") (pintype "passive"))
    )
    (net (code "27") (name "Net-(B2-OUT1)") (class "Default")
      (node (ref "B2") (pin "4") (pinfunction "OUT1_4") (pintype "bidirectional"))
      (node (ref "U4") (pin "8") (pinfunction "RFP_8") (pintype "bidirectional"))
    )
    (net (code "28") (name "Net-(B2-OUT2)") (class "Default")
      (node (ref "B2") (pin "3") (pinfunction "OUT2_3") (pintype "bidirectional"))
      (node (ref "U4") (pin "9") (pinfunction "RFN_9") (pintype "bidirectional"))
    )
    (net (code "29") (name "Net-(C11-Pad1)") (class "Default")
      (node (ref "C11") (pin "1") (pinfunction "1_1") (pintype "passive"))
      (node (ref "U4") (pin "21") (pinfunction "DVDD_21") (pintype "bidirectional"))
      (node (ref "U4") (pin "22") (pinfunction "DVDD_22") (pintype "bidirectional"))
    )
    (net (code "30") (name "Net-(D2-A)") (class "Default")
      (node (ref "D2") (pin "2") (pinfunction "A_2") (pintype "passive"))
      (node (ref "S1") (pin "7") (pinfunction "ON1_7") (pintype "bidirectional"))
    )
    (net (code "31") (name "Net-(D3-A)") (class "Default")
      (node (ref "D3") (pin "2") (pinfunction "A_2") (pintype "passive"))
      (node (ref "R3") (pin "6") (pinfunction "2_6") (pintype "passive"))
      (node (ref "S1") (pin "3") (pinfunction "ON_3") (pintype "bidirectional"))
    )
    (net (code "32") (name "Net-(R1B-2)") (class "Default")
      (node (ref "R1") (pin "6") (pinfunction "2_6") (pintype "passive"))
      (node (ref "U2") (pin "5") (pinfunction "PROG_5") (pintype "input"))
    )
    (net (code "33") (name "Net-(R4A-1)") (class "Default")
      (node (ref "D1") (pin "A1") (pinfunction "A1_A1") (pintype "passive"))
      (node (ref "R4") (pin "4") (pinfunction "1_4") (pintype "passive"))
    )
    (net (code "34") (name "Net-(R4A-2)") (class "Default")
      (node (ref "R4") (pin "5") (pinfunction "2_5") (pintype "passive"))
      (node (ref "R4") (pin "6") (pinfunction "2_6") (pintype "passive"))
      (node (ref "U2") (pin "1") (pinfunction "STAT_1") (pintype "output"))
    )
    (net (code "35") (name "Net-(R4B-1)") (class "Default")
      (node (ref "D1") (pin "C2") (pinfunction "C2_C2") (pintype "passive"))
      (node (ref "R4") (pin "3") (pinfunction "1_3") (pintype "passive"))
    )
    (net (code "36") (name "Net-(R4C-2)") (class "Default")
      (node (ref "D4") (pin "C1") (pinfunction "C1_C1") (pintype "passive"))
      (node (ref "R4") (pin "7") (pinfunction "2_7") (pintype "passive"))
    )
    (net (code "37") (name "Net-(R4D-2)") (class "Default")
      (node (ref "D4") (pin "C2") (pinfunction "C2_C2") (pintype "passive"))
      (node (ref "R4") (pin "8") (pinfunction "2_8") (pintype "passive"))
    )
    (net (code "38") (name "Net-(R5A-1)") (class "Default")
      (node (ref "D5") (pin "A2") (pinfunction "A2_A2") (pintype "passive"))
      (node (ref "R5") (pin "4") (pinfunction "1_4") (pintype "passive"))
    )
    (net (code "39") (name "Net-(R5B-1)") (class "Default")
      (node (ref "D5") (pin "A1") (pinfunction "A1_A1") (pintype "passive"))
      (node (ref "R5") (pin "3") (pinfunction "1_3") (pintype "passive"))
    )
    (net (code "40") (name "Net-(R5C-2)") (class "Default")
      (node (ref "D6") (pin "C1") (pinfunction "C1_C1") (pintype "passive"))
      (node (ref "R5") (pin "7") (pinfunction "2_7") (pintype "passive"))
    )
    (net (code "41") (name "Net-(R5D-2)") (class "Default")
      (node (ref "D6") (pin "C2") (pinfunction "C2_C2") (pintype "passive"))
      (node (ref "R5") (pin "8") (pinfunction "2_8") (pintype "passive"))
    )
    (net (code "42") (name "Net-(S1-C)") (class "Default")
      (node (ref "B3") (pin "P") (pinfunction "P_P") (pintype "bidirectional"))
      (node (ref "C6") (pin "1") (pinfunction "1_1") (pintype "passive"))
      (node (ref "S1") (pin "2") (pinfunction "C_2") (pintype "bidirectional"))
      (node (ref "U2") (pin "3") (pinfunction "VBAT_3") (pintype "power_in"))
      (node (ref "V30") (pin "P1") (pinfunction "N_P1") (pintype "bidirectional"))
      (node (ref "V31") (pin "P1") (pinfunction "N_P1") (pintype "bidirectional"))
      (node (ref "V32") (pin "P1") (pinfunction "N_P1") (pintype "bidirectional"))
      (node (ref "V33") (pin "P1") (pinfunction "N_P1") (pintype "bidirectional"))
      (node (ref "V34") (pin "P1") (pinfunction "N_P1") (pintype "bidirectional"))
      (node (ref "V36") (pin "P1") (pinfunction "N_P1") (pintype "bidirectional"))
      (node (ref "V6") (pin "P1") (pinfunction "N_P1") (pintype "bidirectional"))
    )
    (net (code "43") (name "Net-(S2-C)") (class "Default")
      (node (ref "S2") (pin "2") (pinfunction "C_2") (pintype "bidirectional"))
      (node (ref "U5") (pin "12") (pinfunction "2S_12") (pintype "bidirectional"))
      (node (ref "U5") (pin "4") (pinfunction "1S_4") (pintype "bidirectional"))
    )
    (net (code "44") (name "Net-(U4-AVDD)") (class "Default")
      (node (ref "C13") (pin "1") (pinfunction "1_1") (pintype "passive"))
      (node (ref "U4") (pin "60") (pinfunction "AVDD_60") (pintype "bidirectional"))
    )
    (net (code "45") (name "Net-(U4-PG0(DIG3))") (class "Default")
      (node (ref "D6") (pin "A2") (pinfunction "A2_A2") (pintype "passive"))
      (node (ref "U4") (pin "14") (pinfunction "PG0(DIG3)_14") (pintype "bidirectional"))
    )
    (net (code "46") (name "Net-(U4-PG1(DIG1))") (class "Default")
      (node (ref "D6") (pin "A1") (pinfunction "A1_A1") (pintype "passive"))
      (node (ref "U4") (pin "15") (pinfunction "PG1(DIG1)_15") (pintype "bidirectional"))
    )
    (net (code "47") (name "Net-(U4-XTAL1)") (class "Default")
      (node (ref "C14") (pin "1") (pinfunction "1_1") (pintype "passive"))
      (node (ref "U4") (pin "57") (pinfunction "XTAL1_57") (pintype "bidirectional"))
      (node (ref "Y1") (pin "3") (pinfunction "2_3") (pintype "passive"))
    )
    (net (code "48") (name "Net-(U4-XTAL2)") (class "Default")
      (node (ref "C15") (pin "1") (pinfunction "1_1") (pintype "passive"))
      (node (ref "U4") (pin "56") (pinfunction "XTAL2_56") (pintype "bidirectional"))
      (node (ref "Y1") (pin "1") (pinfunction "1_1") (pintype "passive"))
    )
    (net (code "49") (name "PITCH") (class "Default")
      (node (ref "J3") (pin "V") (pinfunction "V_V") (pintype "bidirectional"))
      (node (ref "J8") (pin "V") (pinfunction "V_V") (pintype "bidirectional"))
      (node (ref "U4") (pin "2") (pinfunction "PF3(ADC3/DIG4)_2") (pintype "bidirectional"))
    )
    (net (code "50") (name "RESET") (class "Default")
      (node (ref "B1") (pin "1") (pinfunction "1_1") (pintype "passive"))
      (node (ref "B1") (pin "2") (pinfunction "1_2") (pintype "passive"))
      (node (ref "C1") (pin "1") (pinfunction "1_1") (pintype "passive"))
      (node (ref "J4") (pin "5") (pinfunction "5_5") (pintype "passive"))
      (node (ref "R3") (pin "1") (pinfunction "1_1") (pintype "passive"))
      (node (ref "U4") (pin "12") (pinfunction "RSTN_12") (pintype "bidirectional"))
    )
    (net (code "51") (name "RF") (class "Default")
      (node (ref "D4") (pin "A2") (pinfunction "A2_A2") (pintype "passive"))
      (node (ref "U4") (pin "16") (pinfunction "PG2(AMR)_16") (pintype "bidirectional"))
    )
    (net (code "52") (name "ROLL") (class "Default")
      (node (ref "J3") (pin "H") (pinfunction "H_H") (pintype "bidirectional"))
      (node (ref "J8") (pin "H") (pinfunction "H_H") (pintype "bidirectional"))
      (node (ref "U4") (pin "1") (pinfunction "PF2(ADC2/DIG2)_1") (pintype "bidirectional"))
    )
    (net (code "53") (name "RXI") (class "Default")
      (node (ref "U3") (pin "5") (pinfunction "RXD_5") (pintype "input"))
      (node (ref "U5") (pin "10") (pinfunction "3Z_10") (pintype "bidirectional"))
    )
    (net (code "54") (name "RXI-0") (class "Default")
      (node (ref "U4") (pin "47") (pinfunction "PE1(TXD0)_47") (pintype "bidirectional"))
      (node (ref "U5") (pin "11") (pinfunction "3Y0_11") (pintype "bidirectional"))
    )
    (net (code "55") (name "RXI-1") (class "Default")
      (node (ref "J5") (pin "RXI") (pinfunction "2_RXI") (pintype "passive"))
      (node (ref "J6") (pin "RXI") (pinfunction "1_RXI") (pintype "bidirectional"))
      (node (ref "U5") (pin "9") (pinfunction "3Y1_9") (pintype "bidirectional"))
    )
    (net (code "56") (name "RXLED") (class "Default")
      (node (ref "D5") (pin "C2") (pinfunction "C2_C2") (pintype "passive"))
      (node (ref "U3") (pin "22") (pinfunction "RXLED_22") (pintype "input"))
    )
    (net (code "57") (name "SCK") (class "Default")
      (node (ref "J4") (pin "3") (pinfunction "3_3") (pintype "passive"))
      (node (ref "U4") (pin "37") (pinfunction "PB1(SCK/PCINT1)_37") (pintype "bidirectional"))
    )
    (net (code "58") (name "SHIELD") (class "Default")
      (node (ref "B12") (pin "P2") (pinfunction "P2_P2") (pintype "bidirectional"))
    )
    (net (code "59") (name "THROTTLE") (class "Default")
      (node (ref "J2") (pin "V") (pinfunction "V_V") (pintype "bidirectional"))
      (node (ref "J7") (pin "V") (pinfunction "V_V") (pintype "bidirectional"))
      (node (ref "U4") (pin "64") (pinfunction "PF1(ADC1)_64") (pintype "bidirectional"))
    )
    (net (code "60") (name "TXLED") (class "Default")
      (node (ref "D5") (pin "C1") (pinfunction "C1_C1") (pintype "passive"))
      (node (ref "U3") (pin "23") (pinfunction "TXLED_23") (pintype "input"))
    )
    (net (code "61") (name "TXO") (class "Default")
      (node (ref "U3") (pin "1") (pinfunction "TXD_1") (pintype "output"))
      (node (ref "U5") (pin "6") (pinfunction "2Z_6") (pintype "bidirectional"))
    )
    (net (code "62") (name "TXO-0") (class "Default")
      (node (ref "U4") (pin "46") (pinfunction "PE0(RXD0/PCINT8)_46") (pintype "bidirectional"))
      (node (ref "U5") (pin "7") (pinfunction "2Y0_7") (pintype "bidirectional"))
    )
    (net (code "63") (name "TXO-1") (class "Default")
      (node (ref "J5") (pin "TXO") (pinfunction "3_TXO") (pintype "passive"))
      (node (ref "J6") (pin "TXO") (pinfunction "2_TXO") (pintype "bidirectional"))
      (node (ref "U5") (pin "5") (pinfunction "2Y1_5") (pintype "bidirectional"))
    )
    (net (code "64") (name "USB_D_N") (class "Default")
      (node (ref "J1") (pin "2") (pinfunction "2-D-_2") (pintype "bidirectional"))
      (node (ref "U3") (pin "16") (pinfunction "USBDM_16") (pintype "bidirectional"))
    )
    (net (code "65") (name "USB_D_P") (class "Default")
      (node (ref "J1") (pin "3") (pinfunction "3-D+_3") (pintype "bidirectional"))
      (node (ref "U3") (pin "15") (pinfunction "USBDP_15") (pintype "bidirectional"))
    )
    (net (code "66") (name "VBUS") (class "Default")
      (node (ref "C5") (pin "1") (pinfunction "1_1") (pintype "passive"))
      (node (ref "D1") (pin "A2") (pinfunction "A2_A2") (pintype "passive"))
      (node (ref "J1") (pin "1") (pinfunction "1-VCC_1") (pintype "bidirectional"))
      (node (ref "P1") (pin "T") (pinfunction "T_T") (pintype "bidirectional"))
      (node (ref "R3") (pin "5") (pinfunction "2_5") (pintype "passive"))
      (node (ref "S1") (pin "6") (pinfunction "C1_6") (pintype "bidirectional"))
      (node (ref "U2") (pin "4") (pinfunction "VDD_4") (pintype "power_in"))
      (node (ref "V1") (pin "P1") (pinfunction "N_P1") (pintype "bidirectional"))
      (node (ref "V2") (pin "P1") (pinfunction "N_P1") (pintype "bidirectional"))
      (node (ref "V23") (pin "P1") (pinfunction "N_P1") (pintype "bidirectional"))
      (node (ref "V24") (pin "P1") (pinfunction "N_P1") (pintype "bidirectional"))
      (node (ref "V26") (pin "P1") (pinfunction "N_P1") (pintype "bidirectional"))
      (node (ref "V27") (pin "P1") (pinfunction "N_P1") (pintype "bidirectional"))
      (node (ref "V28") (pin "P1") (pinfunction "N_P1") (pintype "bidirectional"))
    )
    (net (code "67") (name "VIN") (class "Default")
      (node (ref "C7") (pin "1") (pinfunction "1_1") (pintype "passive"))
      (node (ref "C8") (pin "1") (pinfunction "1_1") (pintype "passive"))
      (node (ref "D2") (pin "1") (pinfunction "C_1") (pintype "passive"))
      (node (ref "D3") (pin "1") (pinfunction "C_1") (pintype "passive"))
      (node (ref "J4") (pin "2") (pinfunction "2_2") (pintype "passive"))
      (node (ref "L1") (pin "RAW") (pinfunction "VIN_RAW") (pintype "bidirectional"))
      (node (ref "P2") (pin "T") (pinfunction "T_T") (pintype "bidirectional"))
      (node (ref "U3") (pin "20") (pinfunction "VCC_20") (pintype "power_in"))
    )
    (net (code "68") (name "YAW") (class "Default")
      (node (ref "J2") (pin "H") (pinfunction "H_H") (pintype "bidirectional"))
      (node (ref "J7") (pin "H") (pinfunction "H_H") (pintype "bidirectional"))
      (node (ref "U4") (pin "63") (pinfunction "PF0(ADC0)_63") (pintype "bidirectional"))
    )
    (net (code "69") (name "unconnected-(J1-4-ID-Pad4)") (class "Default")
      (node (ref "J1") (pin "4") (pinfunction "4-ID_4") (pintype "bidirectional"))
    )
    (net (code "70") (name "unconnected-(L1-PadSCK)") (class "Default")
      (node (ref "L1") (pin "SCK") (pinfunction "SCK_SCK") (pintype "bidirectional"))
    )
    (net (code "71") (name "unconnected-(L1-PadSDI)") (class "Default")
      (node (ref "L1") (pin "SDI") (pinfunction "SDI_SDI") (pintype "bidirectional"))
    )
    (net (code "72") (name "unconnected-(L1-PadSDO)") (class "Default")
      (node (ref "L1") (pin "SDO") (pinfunction "SDO_SDO") (pintype "bidirectional"))
    )
    (net (code "73") (name "unconnected-(L1-Pad{slash}CS)") (class "Default")
      (node (ref "L1") (pin "/CS") (pinfunction "/CS_/CS") (pintype "bidirectional"))
    )
    (net (code "74") (name "unconnected-(L1-SCL-PadCL)") (class "Default")
      (node (ref "L1") (pin "CL") (pinfunction "SCL_CL") (pintype "bidirectional"))
    )
    (net (code "75") (name "unconnected-(L1-SDA-PadDA)") (class "Default")
      (node (ref "L1") (pin "DA") (pinfunction "SDA_DA") (pintype "bidirectional"))
    )
    (net (code "76") (name "unconnected-(S1-OFF-Pad1)") (class "Default")
      (node (ref "S1") (pin "1") (pinfunction "OFF_1") (pintype "bidirectional"))
    )
    (net (code "77") (name "unconnected-(S1-OFF1-Pad5)") (class "Default")
      (node (ref "S1") (pin "5") (pinfunction "OFF1_5") (pintype "bidirectional"))
    )
    (net (code "78") (name "unconnected-(S2-C1-Pad6)") (class "Default")
      (node (ref "S2") (pin "6") (pinfunction "C1_6") (pintype "bidirectional"))
    )
    (net (code "79") (name "unconnected-(S2-OFF1-Pad5)") (class "Default")
      (node (ref "S2") (pin "5") (pinfunction "OFF1_5") (pintype "bidirectional"))
    )
    (net (code "80") (name "unconnected-(S2-ON1-Pad7)") (class "Default")
      (node (ref "S2") (pin "7") (pinfunction "ON1_7") (pintype "bidirectional"))
    )
    (net (code "81") (name "unconnected-(U3-DCD-Pad10)") (class "Default")
      (node (ref "U3") (pin "10") (pinfunction "DCD_10") (pintype "input"))
    )
    (net (code "82") (name "unconnected-(U3-DSR-Pad9)") (class "Default")
      (node (ref "U3") (pin "9") (pinfunction "DSR_9") (pintype "input"))
    )
    (net (code "83") (name "unconnected-(U3-OSCI-Pad27)") (class "Default")
      (node (ref "U3") (pin "27") (pinfunction "OSCI_27") (pintype "input"))
    )
    (net (code "84") (name "unconnected-(U3-OSCO-Pad28)") (class "Default")
      (node (ref "U3") (pin "28") (pinfunction "OSCO_28") (pintype "output"))
    )
    (net (code "85") (name "unconnected-(U3-PWREN-Pad14)") (class "Default")
      (node (ref "U3") (pin "14") (pinfunction "PWREN_14") (pintype "input"))
    )
    (net (code "86") (name "unconnected-(U3-RESET-Pad19)") (class "Default")
      (node (ref "U3") (pin "19") (pinfunction "RESET_19") (pintype "input"))
    )
    (net (code "87") (name "unconnected-(U3-RI-Pad6)") (class "Default")
      (node (ref "U3") (pin "6") (pinfunction "RI_6") (pintype "input"))
    )
    (net (code "88") (name "unconnected-(U3-RTS-Pad3)") (class "Default")
      (node (ref "U3") (pin "3") (pinfunction "RTS_3") (pintype "output"))
    )
    (net (code "89") (name "unconnected-(U3-SLEEP-Pad12)") (class "Default")
      (node (ref "U3") (pin "12") (pinfunction "SLEEP_12") (pintype "input"))
    )
    (net (code "90") (name "unconnected-(U3-TXDEN-Pad13)") (class "Default")
      (node (ref "U3") (pin "13") (pinfunction "TXDEN_13") (pintype "input"))
    )
    (net (code "91") (name "unconnected-(U4-AREF-Pad62)") (class "Default")
      (node (ref "U4") (pin "62") (pinfunction "AREF_62") (pintype "bidirectional"))
    )
    (net (code "92") (name "unconnected-(U4-PB0(SSN{slash}PCINT0)-Pad36)") (class "Default")
      (node (ref "U4") (pin "36") (pinfunction "PB0(SSN/PCINT0)_36") (pintype "bidirectional"))
    )
    (net (code "93") (name "unconnected-(U4-PB6(OC1B{slash}PCINT6)-Pad42)") (class "Default")
      (node (ref "U4") (pin "42") (pinfunction "PB6(OC1B/PCINT6)_42") (pintype "bidirectional"))
    )
    (net (code "94") (name "unconnected-(U4-PB7(OC0A{slash}OC1C{slash}PCINT7)-Pad43)") (class "Default")
      (node (ref "U4") (pin "43") (pinfunction "PB7(OC0A/OC1C/PCINT7)_43") (pintype "bidirectional"))
    )
    (net (code "95") (name "unconnected-(U4-PD4(ICP1)-Pad29)") (class "Default")
      (node (ref "U4") (pin "29") (pinfunction "PD4(ICP1)_29") (pintype "bidirectional"))
    )
    (net (code "96") (name "unconnected-(U4-PD5(XCK1)-Pad30)") (class "Default")
      (node (ref "U4") (pin "30") (pinfunction "PD5(XCK1)_30") (pintype "bidirectional"))
    )
    (net (code "97") (name "unconnected-(U4-PE2(XCK0{slash}AIN0)-Pad48)") (class "Default")
      (node (ref "U4") (pin "48") (pinfunction "PE2(XCK0/AIN0)_48") (pintype "bidirectional"))
    )
    (net (code "98") (name "unconnected-(U4-PE3(OC3A{slash}AIN1)-Pad49)") (class "Default")
      (node (ref "U4") (pin "49") (pinfunction "PE3(OC3A/AIN1)_49") (pintype "bidirectional"))
    )
    (net (code "99") (name "unconnected-(U4-PF4(ADC4{slash}TCK)-Pad3)") (class "Default")
      (node (ref "U4") (pin "3") (pinfunction "PF4(ADC4/TCK)_3") (pintype "bidirectional"))
    )
    (net (code "100") (name "unconnected-(U4-PF5(ADC5{slash}TMS)-Pad4)") (class "Default")
      (node (ref "U4") (pin "4") (pinfunction "PF5(ADC5/TMS)_4") (pintype "bidirectional"))
    )
    (net (code "101") (name "unconnected-(U4-PF6(ADC6{slash}TDO)-Pad5)") (class "Default")
      (node (ref "U4") (pin "5") (pinfunction "PF6(ADC6/TDO)_5") (pintype "bidirectional"))
    )
    (net (code "102") (name "unconnected-(U4-PG3(TOSC2)-Pad17)") (class "Default")
      (node (ref "U4") (pin "17") (pinfunction "PG3(TOSC2)_17") (pintype "bidirectional"))
    )
    (net (code "103") (name "unconnected-(U4-PG4(TOSC1)-Pad18)") (class "Default")
      (node (ref "U4") (pin "18") (pinfunction "PG4(TOSC1)_18") (pintype "bidirectional"))
    )
    (net (code "104") (name "unconnected-(U4-PG5(OC0B)-Pad19)") (class "Default")
      (node (ref "U4") (pin "19") (pinfunction "PG5(OC0B)_19") (pintype "bidirectional"))
    )
    (net (code "105") (name "unconnected-(U4-RSTON-Pad13)") (class "Default")
      (node (ref "U4") (pin "13") (pinfunction "RSTON_13") (pintype "bidirectional"))
    )
  )
)
